# D1_mini_Plus.net
KiCad netlist of a schematic drawn in EAGLE
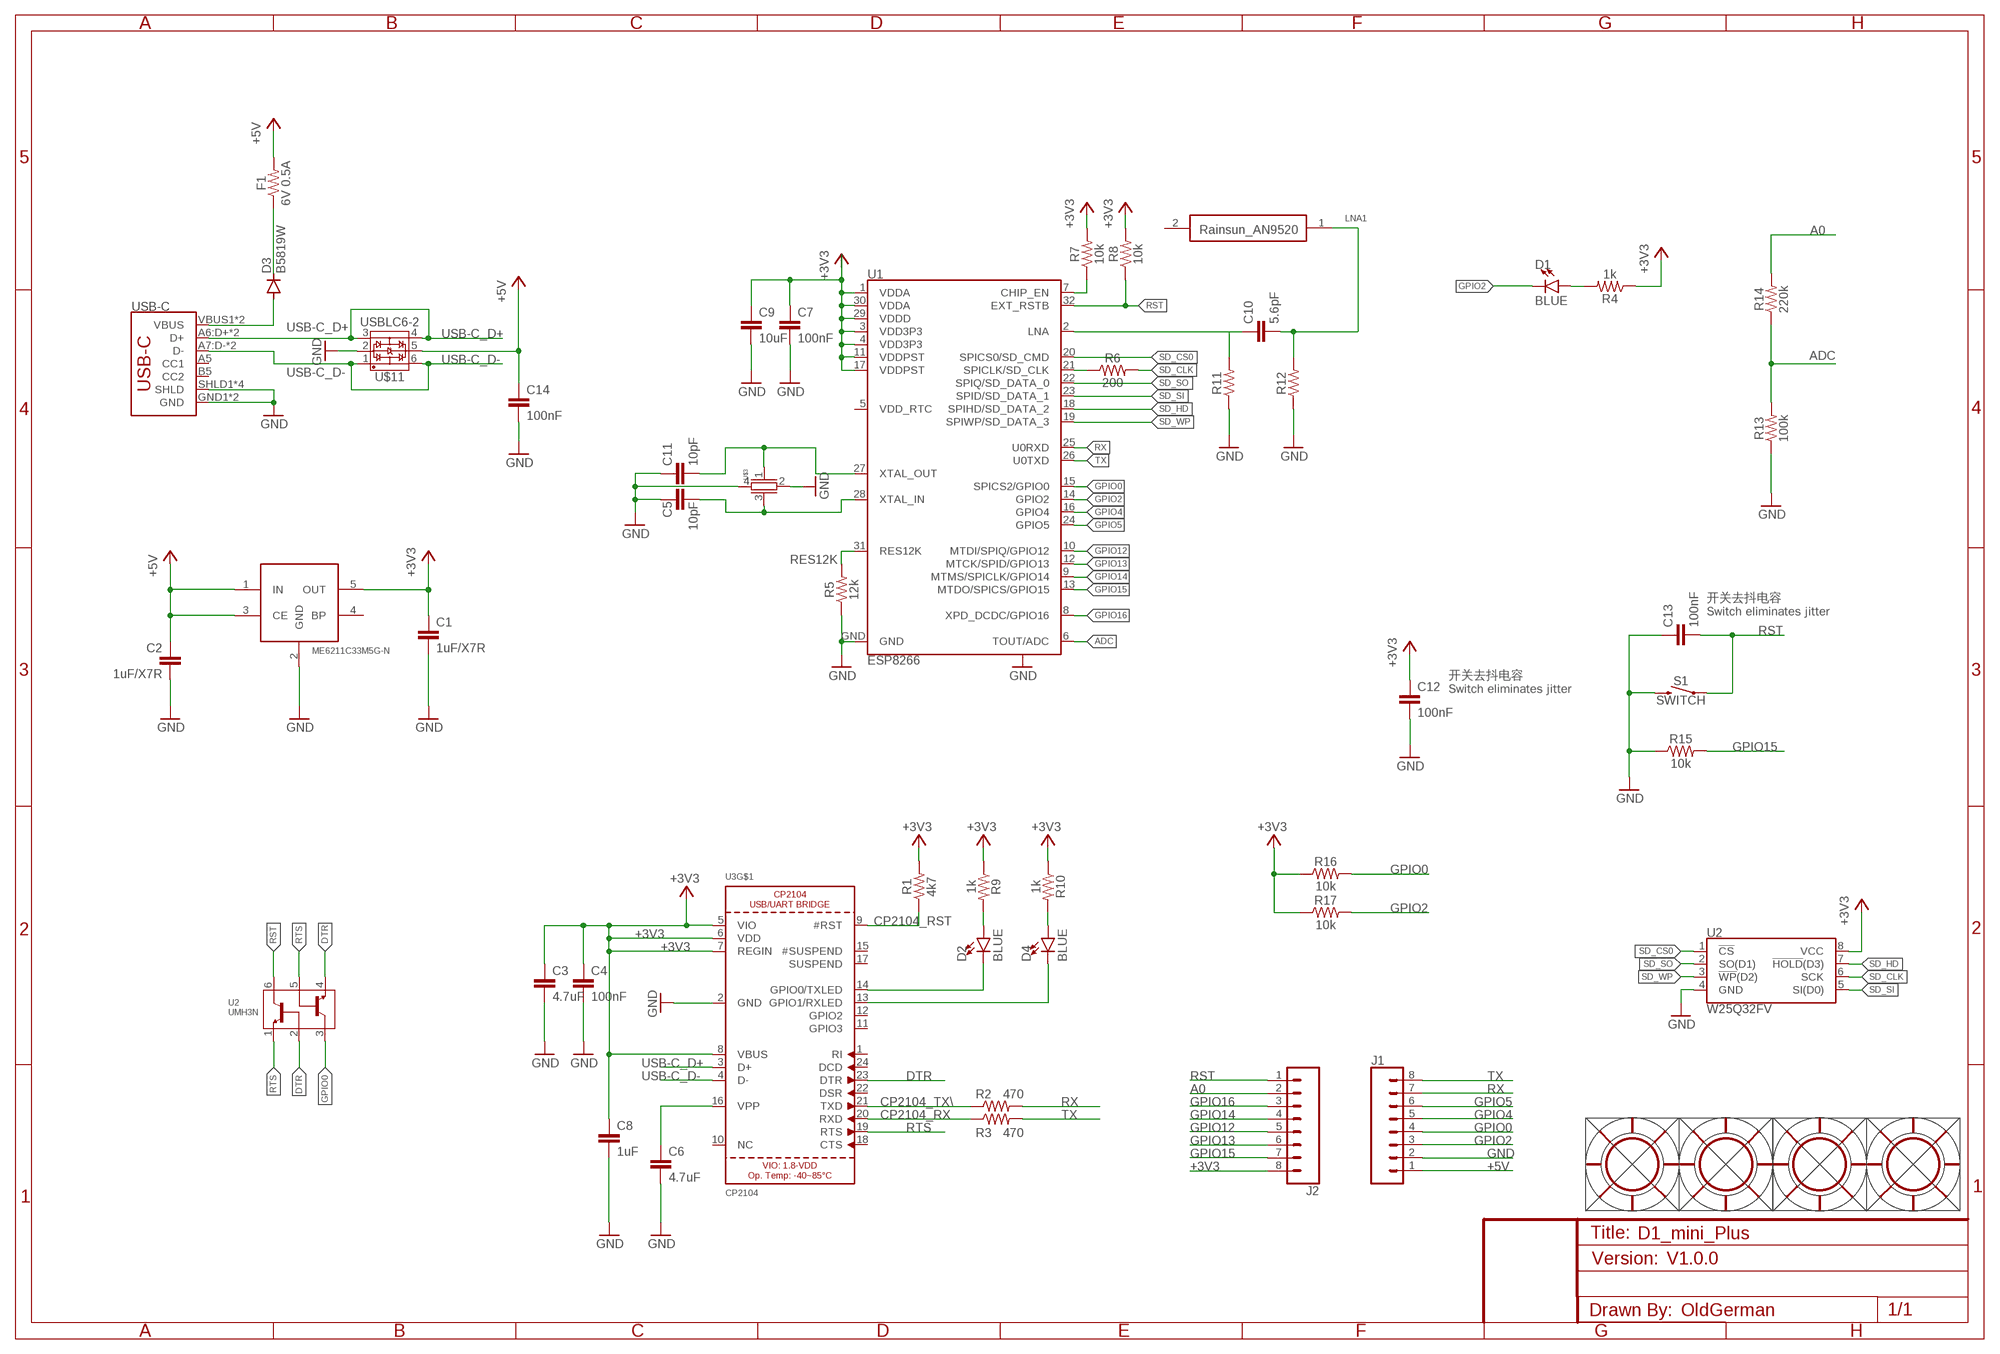
[diagram p0: schematic, sheet 1]

(export (version "E")
  (design (tool "Eeschema 10.0.6"))
  (components
    (comp (ref "C1")
      (value "1uF/X7R")
      (footprint "eagle-import:0603")
      (libsource (lib "eagle-import") (part "CAP-0603"))
    )
    (comp (ref "C2")
      (value "1uF/X7R")
      (footprint "eagle-import:0603")
      (libsource (lib "eagle-import") (part "CAP-0603"))
    )
    (comp (ref "C3")
      (value "4.7uF")
      (footprint "eagle-import:0603")
      (libsource (lib "eagle-import") (part "CAP-0603"))
    )
    (comp (ref "C4")
      (value "100nF")
      (footprint "eagle-import:0603")
      (libsource (lib "eagle-import") (part "CAP-0603"))
    )
    (comp (ref "C5")
      (value "10pF")
      (footprint "eagle-import:0603")
      (libsource (lib "eagle-import") (part "CAP-0603"))
    )
    (comp (ref "C6")
      (value "4.7uF")
      (footprint "eagle-import:0603")
      (libsource (lib "eagle-import") (part "CAP-0603"))
    )
    (comp (ref "C7")
      (value "100nF")
      (footprint "eagle-import:0603")
      (libsource (lib "eagle-import") (part "CAP-0603"))
    )
    (comp (ref "C8")
      (value "1uF")
      (footprint "eagle-import:0603")
      (libsource (lib "eagle-import") (part "CAP-0603"))
    )
    (comp (ref "C9")
      (value "10uF")
      (footprint "eagle-import:0603")
      (libsource (lib "eagle-import") (part "CAP-0603"))
    )
    (comp (ref "C10")
      (value "5.6pF")
      (footprint "eagle-import:0603")
      (libsource (lib "eagle-import") (part "CAP-0603"))
    )
    (comp (ref "C11")
      (value "10pF")
      (footprint "eagle-import:0603")
      (libsource (lib "eagle-import") (part "CAP-0603"))
    )
    (comp (ref "C12")
      (value "100nF")
      (footprint "eagle-import:0603")
      (libsource (lib "eagle-import") (part "CAP-0603"))
    )
    (comp (ref "C13")
      (value "100nF")
      (footprint "eagle-import:0603")
      (libsource (lib "eagle-import") (part "CAP-0603"))
    )
    (comp (ref "C14")
      (value "100nF")
      (footprint "eagle-import:0603")
      (libsource (lib "eagle-import") (part "CAP-0603"))
    )
    (comp (ref "D1")
      (value "BLUE")
      (footprint "eagle-import:LED-0603")
      (libsource (lib "eagle-import") (part "LED-BLUE0603"))
    )
    (comp (ref "D2")
      (value "BLUE")
      (footprint "eagle-import:LED-0603")
      (libsource (lib "eagle-import") (part "LED-BLUE0603"))
    )
    (comp (ref "D3")
      (value "B5819W")
      (footprint "eagle-import:SOD323-R")
      (libsource (lib "eagle-import") (part "DIODE-SOD323-R"))
    )
    (comp (ref "D4")
      (value "BLUE")
      (footprint "eagle-import:LED-0603")
      (libsource (lib "eagle-import") (part "LED-BLUE0603"))
    )
    (comp (ref "F1")
      (value "6V 0.5A")
      (footprint "eagle-import:0603")
      (libsource (lib "eagle-import") (part "RESISTOR0603"))
    )
    (comp (ref "J1")
      (value "CONN_08NO_SILK_FEMALE_PTH")
      (footprint "eagle-import:1X08_NO_SILK")
      (libsource (lib "eagle-import") (part "CONN_08NO_SILK_FEMALE_PTH"))
    )
    (comp (ref "J2")
      (value "CONN_08NO_SILK_FEMALE_PTH")
      (footprint "eagle-import:1X08_NO_SILK")
      (libsource (lib "eagle-import") (part "CONN_08NO_SILK_FEMALE_PTH"))
    )
    (comp (ref "R1")
      (value "4k7")
      (footprint "eagle-import:0603")
      (libsource (lib "eagle-import") (part "RESISTOR0603"))
    )
    (comp (ref "R2")
      (value "470")
      (footprint "eagle-import:0603")
      (libsource (lib "eagle-import") (part "RESISTOR0603"))
    )
    (comp (ref "R3")
      (value "470")
      (footprint "eagle-import:0603")
      (libsource (lib "eagle-import") (part "RESISTOR0603"))
    )
    (comp (ref "R4")
      (value "1k")
      (footprint "eagle-import:0603")
      (libsource (lib "eagle-import") (part "RESISTOR0603"))
    )
    (comp (ref "R5")
      (value "12k")
      (footprint "eagle-import:0603")
      (libsource (lib "eagle-import") (part "RESISTOR0603"))
    )
    (comp (ref "R6")
      (value "200")
      (footprint "eagle-import:0603")
      (libsource (lib "eagle-import") (part "RESISTOR0603"))
    )
    (comp (ref "R7")
      (value "10k")
      (footprint "eagle-import:0603")
      (libsource (lib "eagle-import") (part "RESISTOR0603"))
    )
    (comp (ref "R8")
      (value "10k")
      (footprint "eagle-import:0603")
      (libsource (lib "eagle-import") (part "RESISTOR0603"))
    )
    (comp (ref "R9")
      (value "1k")
      (footprint "eagle-import:0603")
      (libsource (lib "eagle-import") (part "RESISTOR0603"))
    )
    (comp (ref "R10")
      (value "1k")
      (footprint "eagle-import:0603")
      (libsource (lib "eagle-import") (part "RESISTOR0603"))
    )
    (comp (ref "R11")
      (value "RESISTOR0603")
      (footprint "eagle-import:0603")
      (libsource (lib "eagle-import") (part "RESISTOR0603"))
    )
    (comp (ref "R12")
      (value "RESISTOR0603")
      (footprint "eagle-import:0603")
      (libsource (lib "eagle-import") (part "RESISTOR0603"))
    )
    (comp (ref "R13")
      (value "100k")
      (footprint "eagle-import:0603")
      (libsource (lib "eagle-import") (part "RESISTOR0603"))
    )
    (comp (ref "R14")
      (value "220k")
      (footprint "eagle-import:0603")
      (libsource (lib "eagle-import") (part "RESISTOR0603"))
    )
    (comp (ref "R15")
      (value "10k")
      (footprint "eagle-import:0603")
      (libsource (lib "eagle-import") (part "RESISTOR0603"))
    )
    (comp (ref "R16")
      (value "10k")
      (footprint "eagle-import:0603")
      (libsource (lib "eagle-import") (part "RESISTOR0603"))
    )
    (comp (ref "R17")
      (value "10k")
      (footprint "eagle-import:0603")
      (libsource (lib "eagle-import") (part "RESISTOR0603"))
    )
    (comp (ref "S1")
      (value "SWITCH")
      (footprint "eagle-import:TACTILE_SWITCH_SMD_RIGHT_ANGLE")
      (libsource (lib "eagle-import") (part "MOMENTARY-SWITCH-SPST-SMD-RIGHT-ANGLE"))
    )
    (comp (ref "U$1")
      (value "ME6211C33M5G-N")
      (footprint "eagle-import:SOT23-5")
      (libsource (lib "eagle-import") (part "ME6211C33M5G-N"))
    )
    (comp (ref "U$2")
      (value "U2")
      (footprint "eagle-import:SOT363")
      (libsource (lib "eagle-import") (part "UMH3N_DUAL_CRYSTAL"))
    )
    (comp (ref "U$3")
      (value "3225_CRYSTALL")
      (footprint "eagle-import:3.2X2.5_KX-7")
      (libsource (lib "eagle-import") (part "3225_CRYSTALL"))
    )
    (comp (ref "U$4")
      (value "RAINSUN_AT9520")
      (footprint "eagle-import:AN9520")
      (libsource (lib "eagle-import") (part "RAINSUN_AT9520"))
    )
    (comp (ref "U$7")
      (value "SUN-HOLE_2.1")
      (footprint "eagle-import:SUN-HOLE_2.1MM")
      (libsource (lib "eagle-import") (part "SUN-HOLE_2.1"))
    )
    (comp (ref "U$8")
      (value "SUN-HOLE_2.1")
      (footprint "eagle-import:SUN-HOLE_2.1MM")
      (libsource (lib "eagle-import") (part "SUN-HOLE_2.1"))
    )
    (comp (ref "U$9")
      (value "SUN-HOLE_2.1")
      (footprint "eagle-import:SUN-HOLE_2.1MM")
      (libsource (lib "eagle-import") (part "SUN-HOLE_2.1"))
    )
    (comp (ref "U$10")
      (value "SUN-HOLE_2.1")
      (footprint "eagle-import:SUN-HOLE_2.1MM")
      (libsource (lib "eagle-import") (part "SUN-HOLE_2.1"))
    )
    (comp (ref "U$11")
      (value "USBLC6-2")
      (footprint "eagle-import:SOT23-6")
      (libsource (lib "eagle-import") (part "USBLC6-2SOT23-6"))
    )
    (comp (ref "U1")
      (value "ESP8266")
      (footprint "eagle-import:QFN32-5X5MM")
      (libsource (lib "eagle-import") (part "ESP8266"))
    )
    (comp (ref "U2")
      (value "W25Q32FV")
      (footprint "eagle-import:SOIC-8")
      (libsource (lib "eagle-import") (part "W25Q32FVSS"))
    )
    (comp (ref "U3")
      (value "CP2104")
      (footprint "eagle-import:QFN24_4MM_SMSC")
      (fields (field (name "SPICEPREFIX") "X"))
      (libsource (lib "eagle-import") (part "CP2104"))
    )
    (comp (ref "USB-C")
      (value "USB-C_BELOW_BOARD")
      (footprint "eagle-import:USB-C_BLOW_BOARD")
      (libsource (lib "eagle-import") (part "USB-C_BELOW_BOARD"))
    )
  )
  (nets
    (net (code "1") (name "+3V3") (class "Default")
      (node (ref "C1") (pin "1") (pinfunction "1_1") (pintype "passive"))
      (node (ref "C12") (pin "1") (pinfunction "1_1") (pintype "passive"))
      (node (ref "C3") (pin "1") (pinfunction "1_1") (pintype "passive"))
      (node (ref "C4") (pin "1") (pinfunction "1_1") (pintype "passive"))
      (node (ref "C7") (pin "1") (pinfunction "1_1") (pintype "passive"))
      (node (ref "C8") (pin "1") (pinfunction "1_1") (pintype "passive"))
      (node (ref "C9") (pin "1") (pinfunction "1_1") (pintype "passive"))
      (node (ref "J2") (pin "8") (pinfunction "8_8") (pintype "passive"))
      (node (ref "R1") (pin "2") (pinfunction "2_2") (pintype "passive"))
      (node (ref "R10") (pin "1") (pinfunction "1_1") (pintype "passive"))
      (node (ref "R16") (pin "1") (pinfunction "1_1") (pintype "passive"))
      (node (ref "R17") (pin "1") (pinfunction "1_1") (pintype "passive"))
      (node (ref "R4") (pin "1") (pinfunction "1_1") (pintype "passive"))
      (node (ref "R7") (pin "2") (pinfunction "2_2") (pintype "passive"))
      (node (ref "R8") (pin "2") (pinfunction "2_2") (pintype "passive"))
      (node (ref "R9") (pin "1") (pinfunction "1_1") (pintype "passive"))
      (node (ref "U$1") (pin "5") (pinfunction "OUT_5") (pintype "bidirectional"))
      (node (ref "U1") (pin "1") (pinfunction "VDDA_1") (pintype "bidirectional"))
      (node (ref "U1") (pin "11") (pinfunction "VDDPST_11") (pintype "bidirectional"))
      (node (ref "U1") (pin "17") (pinfunction "VDDPST_17") (pintype "bidirectional"))
      (node (ref "U1") (pin "29") (pinfunction "VDDD_29") (pintype "bidirectional"))
      (node (ref "U1") (pin "3") (pinfunction "VDD3P3_3") (pintype "bidirectional"))
      (node (ref "U1") (pin "30") (pinfunction "VDDA_30") (pintype "bidirectional"))
      (node (ref "U1") (pin "4") (pinfunction "VDD3P3_4") (pintype "bidirectional"))
      (node (ref "U2") (pin "8") (pinfunction "VCC_8") (pintype "bidirectional"))
      (node (ref "U3") (pin "5") (pinfunction "VIO_5") (pintype "power_in"))
      (node (ref "U3") (pin "6") (pinfunction "VDD_6") (pintype "power_in"))
      (node (ref "U3") (pin "7") (pinfunction "REGIN_7") (pintype "power_in"))
      (node (ref "U3") (pin "8") (pinfunction "VBUS_8") (pintype "power_in"))
    )
    (net (code "2") (name "+5V") (class "Default")
      (node (ref "C14") (pin "1") (pinfunction "1_1") (pintype "passive"))
      (node (ref "C2") (pin "1") (pinfunction "1_1") (pintype "passive"))
      (node (ref "F1") (pin "2") (pinfunction "2_2") (pintype "passive"))
      (node (ref "J1") (pin "1") (pinfunction "1_1") (pintype "passive"))
      (node (ref "U$1") (pin "1") (pinfunction "IN_1") (pintype "bidirectional"))
      (node (ref "U$1") (pin "3") (pinfunction "CE_3") (pintype "bidirectional"))
      (node (ref "U$11") (pin "5") (pinfunction "P$5_5") (pintype "bidirectional"))
    )
    (net (code "3") (name "/A0") (class "Default")
      (node (ref "J2") (pin "2") (pinfunction "2_2") (pintype "passive"))
      (node (ref "R14") (pin "2") (pinfunction "2_2") (pintype "passive"))
    )
    (net (code "4") (name "/CP2104_RST") (class "Default")
      (node (ref "R1") (pin "1") (pinfunction "1_1") (pintype "passive"))
      (node (ref "U3") (pin "9") (pinfunction "#RST_9") (pintype "bidirectional"))
    )
    (net (code "5") (name "/CP2104_RX") (class "Default")
      (node (ref "R3") (pin "1") (pinfunction "1_1") (pintype "passive"))
      (node (ref "U3") (pin "20") (pinfunction "RXD_20") (pintype "input"))
    )
    (net (code "6") (name "/CP2104_TX\\") (class "Default")
      (node (ref "R2") (pin "1") (pinfunction "1_1") (pintype "passive"))
      (node (ref "U3") (pin "21") (pinfunction "TXD_21") (pintype "output"))
    )
    (net (code "7") (name "/LNA1") (class "Default")
      (node (ref "C10") (pin "2") (pinfunction "2_2") (pintype "passive"))
      (node (ref "R12") (pin "2") (pinfunction "2_2") (pintype "passive"))
      (node (ref "U$4") (pin "1") (pinfunction "P$1_1") (pintype "bidirectional"))
    )
    (net (code "8") (name "/RES12K") (class "Default")
      (node (ref "R5") (pin "2") (pinfunction "2_2") (pintype "passive"))
      (node (ref "U1") (pin "31") (pinfunction "RES12K_31") (pintype "bidirectional"))
    )
    (net (code "9") (name "/USB-C_D+") (class "Default")
      (node (ref "U$11") (pin "3") (pinfunction "P$3_3") (pintype "bidirectional"))
      (node (ref "U$11") (pin "4") (pinfunction "P$4_4") (pintype "bidirectional"))
      (node (ref "U3") (pin "3") (pinfunction "D+_3") (pintype "bidirectional"))
      (node (ref "USB-C") (pin "A6:D+") (pinfunction "D+_A6:D+") (pintype "bidirectional"))
      (node (ref "USB-C") (pin "B6:D+") (pinfunction "D+_B6:D+") (pintype "bidirectional"))
    )
    (net (code "10") (name "/USB-C_D-") (class "Default")
      (node (ref "U$11") (pin "1") (pinfunction "P$1_1") (pintype "bidirectional"))
      (node (ref "U$11") (pin "6") (pinfunction "P$6_6") (pintype "bidirectional"))
      (node (ref "U3") (pin "4") (pinfunction "D-_4") (pintype "bidirectional"))
      (node (ref "USB-C") (pin "A7:D-") (pinfunction "D-_A7:D-") (pintype "bidirectional"))
      (node (ref "USB-C") (pin "B7:D-") (pinfunction "D-_B7:D-") (pintype "bidirectional"))
    )
    (net (code "11") (name "ADC") (class "Default")
      (node (ref "R13") (pin "2") (pinfunction "2_2") (pintype "passive"))
      (node (ref "R14") (pin "1") (pinfunction "1_1") (pintype "passive"))
      (node (ref "U1") (pin "6") (pinfunction "TOUT/ADC_6") (pintype "bidirectional"))
    )
    (net (code "12") (name "DTR") (class "Default")
      (node (ref "U$2") (pin "2") (pinfunction "P$2_2") (pintype "bidirectional"))
      (node (ref "U$2") (pin "4") (pinfunction "P$4_4") (pintype "bidirectional"))
      (node (ref "U3") (pin "23") (pinfunction "DTR_23") (pintype "output"))
    )
    (net (code "13") (name "GND") (class "Default")
      (node (ref "C1") (pin "2") (pinfunction "2_2") (pintype "passive"))
      (node (ref "C11") (pin "1") (pinfunction "1_1") (pintype "passive"))
      (node (ref "C12") (pin "2") (pinfunction "2_2") (pintype "passive"))
      (node (ref "C13") (pin "1") (pinfunction "1_1") (pintype "passive"))
      (node (ref "C14") (pin "2") (pinfunction "2_2") (pintype "passive"))
      (node (ref "C2") (pin "2") (pinfunction "2_2") (pintype "passive"))
      (node (ref "C3") (pin "2") (pinfunction "2_2") (pintype "passive"))
      (node (ref "C4") (pin "2") (pinfunction "2_2") (pintype "passive"))
      (node (ref "C5") (pin "1") (pinfunction "1_1") (pintype "passive"))
      (node (ref "C6") (pin "2") (pinfunction "2_2") (pintype "passive"))
      (node (ref "C7") (pin "2") (pinfunction "2_2") (pintype "passive"))
      (node (ref "C8") (pin "2") (pinfunction "2_2") (pintype "passive"))
      (node (ref "C9") (pin "2") (pinfunction "2_2") (pintype "passive"))
      (node (ref "J1") (pin "2") (pinfunction "2_2") (pintype "passive"))
      (node (ref "R11") (pin "1") (pinfunction "1_1") (pintype "passive"))
      (node (ref "R12") (pin "1") (pinfunction "1_1") (pintype "passive"))
      (node (ref "R13") (pin "1") (pinfunction "1_1") (pintype "passive"))
      (node (ref "R15") (pin "1") (pinfunction "1_1") (pintype "passive"))
      (node (ref "R5") (pin "1") (pinfunction "1_1") (pintype "passive"))
      (node (ref "S1") (pin "2") (pinfunction "2_2") (pintype "passive"))
      (node (ref "U$1") (pin "2") (pinfunction "GND_2") (pintype "bidirectional"))
      (node (ref "U$11") (pin "2") (pinfunction "P$2_2") (pintype "bidirectional"))
      (node (ref "U$3") (pin "2") (pinfunction "P$3_2") (pintype "power_in"))
      (node (ref "U$3") (pin "4") (pinfunction "P$4_4") (pintype "power_in"))
      (node (ref "U1") (pin "GND") (pinfunction "GND_GND") (pintype "bidirectional"))
      (node (ref "U2") (pin "4") (pinfunction "GND_4") (pintype "bidirectional"))
      (node (ref "U3") (pin "2") (pinfunction "GND_2") (pintype "power_in"))
      (node (ref "USB-C") (pin "GND1") (pinfunction "GND_GND1") (pintype "bidirectional"))
      (node (ref "USB-C") (pin "GND2") (pinfunction "GND_GND2") (pintype "bidirectional"))
      (node (ref "USB-C") (pin "SHLD1") (pinfunction "SHLD_SHLD1") (pintype "bidirectional"))
      (node (ref "USB-C") (pin "SHLD2") (pinfunction "SHLD_SHLD2") (pintype "bidirectional"))
      (node (ref "USB-C") (pin "SHLD3") (pinfunction "SHLD_SHLD3") (pintype "bidirectional"))
      (node (ref "USB-C") (pin "SHLD4") (pinfunction "SHLD_SHLD4") (pintype "bidirectional"))
    )
    (net (code "14") (name "GPIO0") (class "Default")
      (node (ref "J1") (pin "4") (pinfunction "4_4") (pintype "passive"))
      (node (ref "R16") (pin "2") (pinfunction "2_2") (pintype "passive"))
      (node (ref "U$2") (pin "3") (pinfunction "P$3_3") (pintype "bidirectional"))
      (node (ref "U1") (pin "15") (pinfunction "SPICS2/GPIO0_15") (pintype "bidirectional"))
    )
    (net (code "15") (name "GPIO2") (class "Default")
      (node (ref "D1") (pin "C") (pinfunction "C_C") (pintype "passive"))
      (node (ref "J1") (pin "3") (pinfunction "3_3") (pintype "passive"))
      (node (ref "R17") (pin "2") (pinfunction "2_2") (pintype "passive"))
      (node (ref "U1") (pin "14") (pinfunction "GPIO2_14") (pintype "bidirectional"))
    )
    (net (code "16") (name "GPIO4") (class "Default")
      (node (ref "J1") (pin "5") (pinfunction "5_5") (pintype "passive"))
      (node (ref "U1") (pin "16") (pinfunction "GPIO4_16") (pintype "bidirectional"))
    )
    (net (code "17") (name "GPIO5") (class "Default")
      (node (ref "J1") (pin "6") (pinfunction "6_6") (pintype "passive"))
      (node (ref "U1") (pin "24") (pinfunction "GPIO5_24") (pintype "bidirectional"))
    )
    (net (code "18") (name "GPIO12") (class "Default")
      (node (ref "J2") (pin "5") (pinfunction "5_5") (pintype "passive"))
      (node (ref "U1") (pin "10") (pinfunction "MTDI/SPIQ/GPIO12_10") (pintype "bidirectional"))
    )
    (net (code "19") (name "GPIO13") (class "Default")
      (node (ref "J2") (pin "6") (pinfunction "6_6") (pintype "passive"))
      (node (ref "U1") (pin "12") (pinfunction "MTCK/SPID/GPIO13_12") (pintype "bidirectional"))
    )
    (net (code "20") (name "GPIO14") (class "Default")
      (node (ref "J2") (pin "4") (pinfunction "4_4") (pintype "passive"))
      (node (ref "U1") (pin "9") (pinfunction "MTMS/SPICLK/GPIO14_9") (pintype "bidirectional"))
    )
    (net (code "21") (name "GPIO15") (class "Default")
      (node (ref "J2") (pin "7") (pinfunction "7_7") (pintype "passive"))
      (node (ref "R15") (pin "2") (pinfunction "2_2") (pintype "passive"))
      (node (ref "U1") (pin "13") (pinfunction "MTDO/SPICS/GPIO15_13") (pintype "bidirectional"))
    )
    (net (code "22") (name "GPIO16") (class "Default")
      (node (ref "J2") (pin "3") (pinfunction "3_3") (pintype "passive"))
      (node (ref "U1") (pin "8") (pinfunction "XPD_DCDC/GPIO16_8") (pintype "bidirectional"))
    )
    (net (code "23") (name "Net-(D1-PadA)") (class "Default")
      (node (ref "D1") (pin "A") (pinfunction "A_A") (pintype "passive"))
      (node (ref "R4") (pin "2") (pinfunction "2_2") (pintype "passive"))
    )
    (net (code "24") (name "Net-(D2-PadA)") (class "Default")
      (node (ref "D2") (pin "A") (pinfunction "A_A") (pintype "passive"))
      (node (ref "R9") (pin "2") (pinfunction "2_2") (pintype "passive"))
    )
    (net (code "25") (name "Net-(D3-PadA)") (class "Default")
      (node (ref "D3") (pin "A") (pinfunction "A_A") (pintype "passive"))
      (node (ref "USB-C") (pin "VBUS1") (pinfunction "VBUS_VBUS1") (pintype "bidirectional"))
      (node (ref "USB-C") (pin "VBUS2") (pinfunction "VBUS_VBUS2") (pintype "bidirectional"))
    )
    (net (code "26") (name "Net-(D3-PadC)") (class "Default")
      (node (ref "D3") (pin "C") (pinfunction "C_C") (pintype "passive"))
      (node (ref "F1") (pin "1") (pinfunction "1_1") (pintype "passive"))
    )
    (net (code "27") (name "Net-(D4-PadA)") (class "Default")
      (node (ref "D4") (pin "A") (pinfunction "A_A") (pintype "passive"))
      (node (ref "R10") (pin "2") (pinfunction "2_2") (pintype "passive"))
    )
    (net (code "28") (name "Net-(U$3-P$1)") (class "Default")
      (node (ref "C11") (pin "2") (pinfunction "2_2") (pintype "passive"))
      (node (ref "U$3") (pin "1") (pinfunction "P$1_1") (pintype "bidirectional"))
      (node (ref "U1") (pin "27") (pinfunction "XTAL_OUT_27") (pintype "bidirectional"))
    )
    (net (code "29") (name "Net-(U$3-P$2)") (class "Default")
      (node (ref "C5") (pin "2") (pinfunction "2_2") (pintype "passive"))
      (node (ref "U$3") (pin "3") (pinfunction "P$2_3") (pintype "bidirectional"))
      (node (ref "U1") (pin "28") (pinfunction "XTAL_IN_28") (pintype "bidirectional"))
    )
    (net (code "30") (name "Net-(U1-CHIP_EN)") (class "Default")
      (node (ref "R7") (pin "1") (pinfunction "1_1") (pintype "passive"))
      (node (ref "U1") (pin "7") (pinfunction "CHIP_EN_7") (pintype "bidirectional"))
    )
    (net (code "31") (name "Net-(U1-LNA)") (class "Default")
      (node (ref "C10") (pin "1") (pinfunction "1_1") (pintype "passive"))
      (node (ref "R11") (pin "2") (pinfunction "2_2") (pintype "passive"))
      (node (ref "U1") (pin "2") (pinfunction "LNA_2") (pintype "bidirectional"))
    )
    (net (code "32") (name "Net-(U1-SPICLK{slash}SD_CLK)") (class "Default")
      (node (ref "R6") (pin "1") (pinfunction "1_1") (pintype "passive"))
      (node (ref "U1") (pin "21") (pinfunction "SPICLK/SD_CLK_21") (pintype "bidirectional"))
    )
    (net (code "33") (name "Net-(U3A-GPIO0{slash}TXLED)") (class "Default")
      (node (ref "D2") (pin "C") (pinfunction "C_C") (pintype "passive"))
      (node (ref "U3") (pin "14") (pinfunction "GPIO0/TXLED_14") (pintype "bidirectional"))
    )
    (net (code "34") (name "Net-(U3A-GPIO1{slash}RXLED)") (class "Default")
      (node (ref "D4") (pin "C") (pinfunction "C_C") (pintype "passive"))
      (node (ref "U3") (pin "13") (pinfunction "GPIO1/RXLED_13") (pintype "bidirectional"))
    )
    (net (code "35") (name "Net-(U3A-VPP)") (class "Default")
      (node (ref "C6") (pin "1") (pinfunction "1_1") (pintype "passive"))
      (node (ref "U3") (pin "16") (pinfunction "VPP_16") (pintype "bidirectional"))
    )
    (net (code "36") (name "RST") (class "Default")
      (node (ref "C13") (pin "2") (pinfunction "2_2") (pintype "passive"))
      (node (ref "J2") (pin "1") (pinfunction "1_1") (pintype "passive"))
      (node (ref "R8") (pin "1") (pinfunction "1_1") (pintype "passive"))
      (node (ref "S1") (pin "1") (pinfunction "1_1") (pintype "passive"))
      (node (ref "U$2") (pin "6") (pinfunction "P$6_6") (pintype "bidirectional"))
      (node (ref "U1") (pin "32") (pinfunction "EXT_RSTB_32") (pintype "bidirectional"))
    )
    (net (code "37") (name "RTS") (class "Default")
      (node (ref "U$2") (pin "1") (pinfunction "P$1_1") (pintype "bidirectional"))
      (node (ref "U$2") (pin "5") (pinfunction "P$5_5") (pintype "bidirectional"))
      (node (ref "U3") (pin "19") (pinfunction "RTS_19") (pintype "output"))
    )
    (net (code "38") (name "RX") (class "Default")
      (node (ref "J1") (pin "7") (pinfunction "7_7") (pintype "passive"))
      (node (ref "R2") (pin "2") (pinfunction "2_2") (pintype "passive"))
      (node (ref "U1") (pin "25") (pinfunction "U0RXD_25") (pintype "bidirectional"))
    )
    (net (code "39") (name "SD_CLK") (class "Default")
      (node (ref "R6") (pin "2") (pinfunction "2_2") (pintype "passive"))
      (node (ref "U2") (pin "6") (pinfunction "SCK_6") (pintype "bidirectional"))
    )
    (net (code "40") (name "SD_CS0") (class "Default")
      (node (ref "U1") (pin "20") (pinfunction "SPICS0/SD_CMD_20") (pintype "bidirectional"))
      (node (ref "U2") (pin "1") (pinfunction "~{CS}_1") (pintype "bidirectional"))
    )
    (net (code "41") (name "SD_HD") (class "Default")
      (node (ref "U1") (pin "18") (pinfunction "SPIHD/SD_DATA_2_18") (pintype "bidirectional"))
      (node (ref "U2") (pin "7") (pinfunction "~{HOLD}(D3)_7") (pintype "bidirectional"))
    )
    (net (code "42") (name "SD_SI") (class "Default")
      (node (ref "U1") (pin "23") (pinfunction "SPID/SD_DATA_1_23") (pintype "bidirectional"))
      (node (ref "U2") (pin "5") (pinfunction "SI(D0)_5") (pintype "bidirectional"))
    )
    (net (code "43") (name "SD_SO") (class "Default")
      (node (ref "U1") (pin "22") (pinfunction "SPIQ/SD_DATA_0_22") (pintype "bidirectional"))
      (node (ref "U2") (pin "2") (pinfunction "SO(D1)_2") (pintype "bidirectional"))
    )
    (net (code "44") (name "SD_WP") (class "Default")
      (node (ref "U1") (pin "19") (pinfunction "SPIWP/SD_DATA_3_19") (pintype "bidirectional"))
      (node (ref "U2") (pin "3") (pinfunction "~{WP}(D2)_3") (pintype "bidirectional"))
    )
    (net (code "45") (name "TX") (class "Default")
      (node (ref "J1") (pin "8") (pinfunction "8_8") (pintype "passive"))
      (node (ref "R3") (pin "2") (pinfunction "2_2") (pintype "passive"))
      (node (ref "U1") (pin "26") (pinfunction "U0TXD_26") (pintype "bidirectional"))
    )
    (net (code "46") (name "unconnected-(U$1-BP-Pad4)") (class "Default")
      (node (ref "U$1") (pin "4") (pinfunction "BP_4") (pintype "bidirectional"))
    )
    (net (code "47") (name "unconnected-(U$4-P$2-Pad2)") (class "Default")
      (node (ref "U$4") (pin "2") (pinfunction "P$2_2") (pintype "no_connect"))
    )
    (net (code "48") (name "unconnected-(U1-VDD_RTC-Pad5)") (class "Default")
      (node (ref "U1") (pin "5") (pinfunction "VDD_RTC_5") (pintype "bidirectional"))
    )
    (net (code "49") (name "unconnected-(U3A-#SUSPEND-Pad15)") (class "Default")
      (node (ref "U3") (pin "15") (pinfunction "#SUSPEND_15") (pintype "output"))
    )
    (net (code "50") (name "unconnected-(U3A-CTS-Pad18)") (class "Default")
      (node (ref "U3") (pin "18") (pinfunction "CTS_18") (pintype "input"))
    )
    (net (code "51") (name "unconnected-(U3A-DCD-Pad24)") (class "Default")
      (node (ref "U3") (pin "24") (pinfunction "DCD_24") (pintype "input"))
    )
    (net (code "52") (name "unconnected-(U3A-DSR-Pad22)") (class "Default")
      (node (ref "U3") (pin "22") (pinfunction "DSR_22") (pintype "input"))
    )
    (net (code "53") (name "unconnected-(U3A-GPIO2-Pad12)") (class "Default")
      (node (ref "U3") (pin "12") (pinfunction "GPIO2_12") (pintype "bidirectional"))
    )
    (net (code "54") (name "unconnected-(U3A-GPIO3-Pad11)") (class "Default")
      (node (ref "U3") (pin "11") (pinfunction "GPIO3_11") (pintype "bidirectional"))
    )
    (net (code "55") (name "unconnected-(U3A-NC-Pad10)") (class "Default")
      (node (ref "U3") (pin "10") (pinfunction "NC_10") (pintype "no_connect"))
    )
    (net (code "56") (name "unconnected-(U3A-RI-Pad1)") (class "Default")
      (node (ref "U3") (pin "1") (pinfunction "RI_1") (pintype "input"))
    )
    (net (code "57") (name "unconnected-(U3A-SUSPEND-Pad17)") (class "Default")
      (node (ref "U3") (pin "17") (pinfunction "SUSPEND_17") (pintype "output"))
    )
    (net (code "58") (name "unconnected-(USB-C-CC1-PadA5)") (class "Default")
      (node (ref "USB-C") (pin "A5") (pinfunction "CC1_A5") (pintype "bidirectional"))
    )
    (net (code "59") (name "unconnected-(USB-C-CC2-PadB5)") (class "Default")
      (node (ref "USB-C") (pin "B5") (pinfunction "CC2_B5") (pintype "bidirectional"))
    )
  )
)
